# LS1_audio.net
KiCad netlist of a schematic drawn in Altium Designer
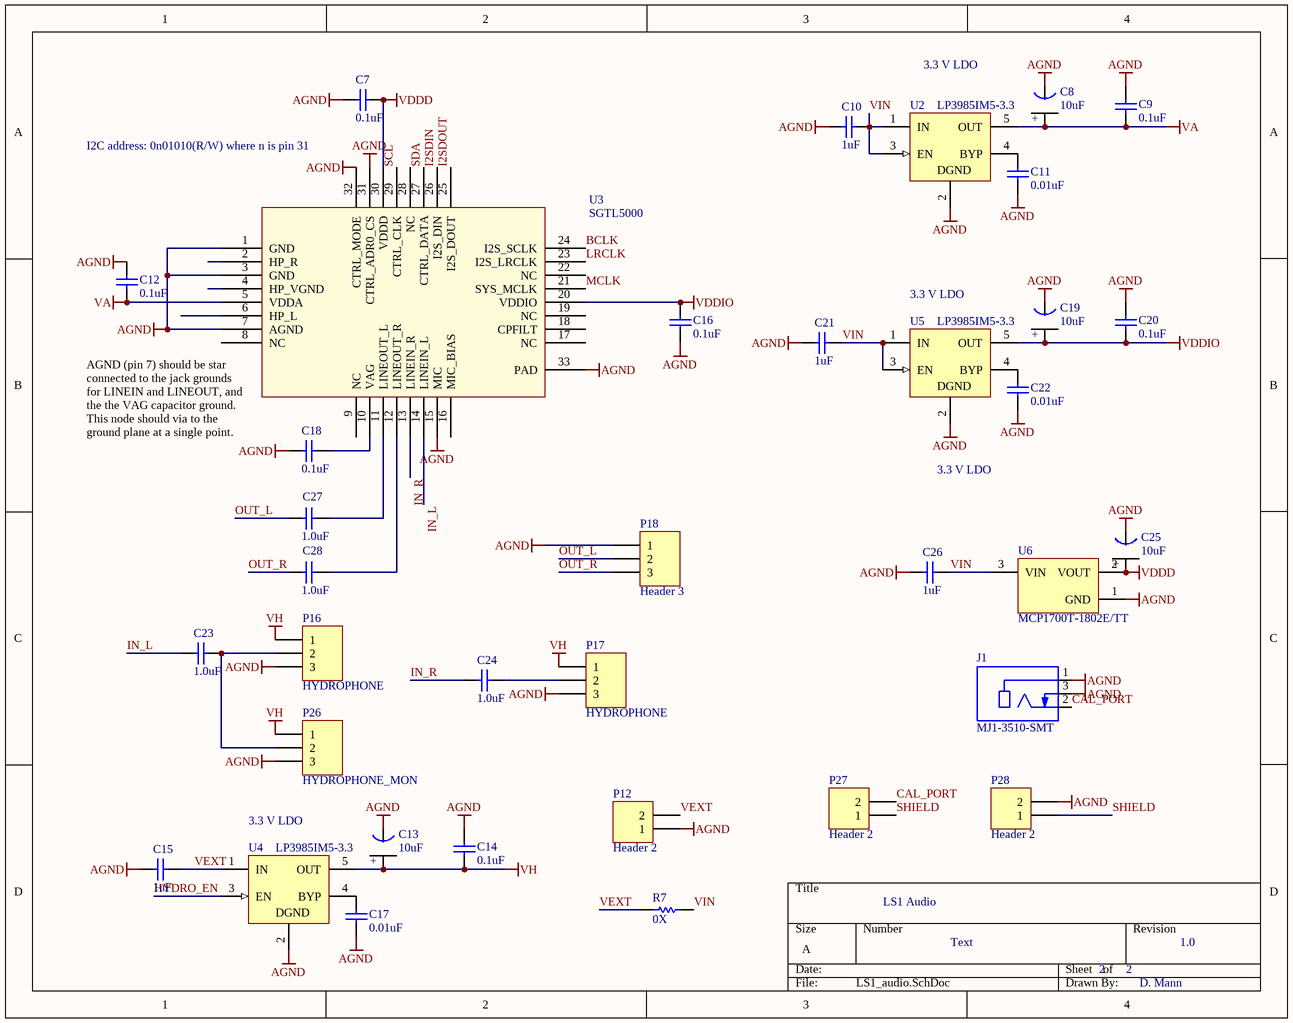
[diagram p0: LS1_audio.SchDoc]

(export (version "E")
  (design (tool "Eeschema 10.0.6"))
  (components
    (comp (ref "C7")
      (value "0.1uF")
      (footprint "0402")
      (description "Ceramic Chip Capacitor - Standard")
      (fields (field (name "PUBLISHER") "Altium Limited"))
      (libsource (lib "KEMET Chip Capacitor") (part "C0402"))
    )
    (comp (ref "C8") (value "10uF") (footprint "Tant0805") (libsource (lib "Loggerhead") (part "Tant0805")))
    (comp (ref "C9")
      (value "0.1uF")
      (footprint "0402")
      (description "Ceramic Chip Capacitor - Standard")
      (fields (field (name "PUBLISHER") "Altium Limited"))
      (libsource (lib "KEMET Chip Capacitor") (part "C0402"))
    )
    (comp (ref "C10")
      (value "1uF")
      (footprint "0402")
      (description "Ceramic Chip Capacitor - Standard")
      (fields (field (name "PUBLISHER") "Altium Limited"))
      (libsource (lib "KEMET Chip Capacitor") (part "C0402"))
    )
    (comp (ref "C11")
      (value "0.01uF")
      (footprint "0402")
      (description "Ceramic Chip Capacitor - Standard")
      (fields (field (name "PUBLISHER") "Altium Limited"))
      (libsource (lib "KEMET Chip Capacitor") (part "C0402"))
    )
    (comp (ref "C12")
      (value "0.1uF")
      (footprint "0402")
      (description "Ceramic Chip Capacitor - Standard")
      (fields (field (name "PUBLISHER") "Altium Limited"))
      (libsource (lib "KEMET Chip Capacitor") (part "C0402"))
    )
    (comp (ref "C13") (value "10uF") (footprint "Tant0805") (libsource (lib "Loggerhead") (part "Tant0805")))
    (comp (ref "C14")
      (value "0.1uF")
      (footprint "0402")
      (description "Ceramic Chip Capacitor - Standard")
      (fields (field (name "PUBLISHER") "Altium Limited"))
      (libsource (lib "KEMET Chip Capacitor") (part "C0402"))
    )
    (comp (ref "C15")
      (value "1uF")
      (footprint "0402")
      (description "Ceramic Chip Capacitor - Standard")
      (fields (field (name "PUBLISHER") "Altium Limited"))
      (libsource (lib "KEMET Chip Capacitor") (part "C0402"))
    )
    (comp (ref "C16")
      (value "0.1uF")
      (footprint "0402")
      (description "Ceramic Chip Capacitor - Standard")
      (fields (field (name "PUBLISHER") "Altium Limited"))
      (libsource (lib "KEMET Chip Capacitor") (part "C0402"))
    )
    (comp (ref "C17")
      (value "0.01uF")
      (footprint "0402")
      (description "Ceramic Chip Capacitor - Standard")
      (fields (field (name "PUBLISHER") "Altium Limited"))
      (libsource (lib "KEMET Chip Capacitor") (part "C0402"))
    )
    (comp (ref "C18")
      (value "0.1uF")
      (footprint "0402")
      (description "Ceramic Chip Capacitor - Standard")
      (fields (field (name "PUBLISHER") "Altium Limited"))
      (libsource (lib "KEMET Chip Capacitor") (part "C0402"))
    )
    (comp (ref "C19") (value "10uF") (footprint "Tant0805") (libsource (lib "Loggerhead") (part "Tant0805")))
    (comp (ref "C20")
      (value "0.1uF")
      (footprint "0402")
      (description "Ceramic Chip Capacitor - Standard")
      (fields (field (name "PUBLISHER") "Altium Limited"))
      (libsource (lib "KEMET Chip Capacitor") (part "C0402"))
    )
    (comp (ref "C21")
      (value "1uF")
      (footprint "0402")
      (description "Ceramic Chip Capacitor - Standard")
      (fields (field (name "PUBLISHER") "Altium Limited"))
      (libsource (lib "KEMET Chip Capacitor") (part "C0402"))
    )
    (comp (ref "C22")
      (value "0.01uF")
      (footprint "0402")
      (description "Ceramic Chip Capacitor - Standard")
      (fields (field (name "PUBLISHER") "Altium Limited"))
      (libsource (lib "KEMET Chip Capacitor") (part "C0402"))
    )
    (comp (ref "C23")
      (value "1.0uF")
      (footprint "0402")
      (description "Ceramic Chip Capacitor - Standard")
      (fields (field (name "PUBLISHER") "Altium Limited"))
      (libsource (lib "KEMET Chip Capacitor") (part "C0402"))
    )
    (comp (ref "C24")
      (value "1.0uF")
      (footprint "0402")
      (description "Ceramic Chip Capacitor - Standard")
      (fields (field (name "PUBLISHER") "Altium Limited"))
      (libsource (lib "KEMET Chip Capacitor") (part "C0402"))
    )
    (comp (ref "C25") (value "10uF") (footprint "Tant0805") (libsource (lib "Loggerhead") (part "Tant0805")))
    (comp (ref "C26")
      (value "1uF")
      (footprint "0402")
      (description "Ceramic Chip Capacitor - Standard")
      (fields (field (name "PUBLISHER") "Altium Limited"))
      (libsource (lib "KEMET Chip Capacitor") (part "C0402"))
    )
    (comp (ref "C27")
      (value "1.0uF")
      (footprint "0402")
      (description "Ceramic Chip Capacitor - Standard")
      (fields (field (name "PUBLISHER") "Altium Limited"))
      (libsource (lib "KEMET Chip Capacitor") (part "C0402"))
    )
    (comp (ref "C28")
      (value "1.0uF")
      (footprint "0402")
      (description "Ceramic Chip Capacitor - Standard")
      (fields (field (name "PUBLISHER") "Altium Limited"))
      (libsource (lib "KEMET Chip Capacitor") (part "C0402"))
    )
    (comp (ref "J1")
      (value "MJ1-3510-SMT")
      (footprint "CUI_MJ1-3510-SMT")
      (description "3.5 mm, Mono, Right Angle, Surface Mount (SMT), Audio Jack Connector")
      (fields (field (name "MF") "{'manufacturer': u'CUI'}"))
      (libsource (lib "MJ1-3510-SMT") (part "MJ1-3510-SMT"))
    )
    (comp (ref "P12")
      (value "Header 2")
      (footprint "HDR1X2")
      (description "Header, 2-Pin")
      (fields (field (name "PUBLISHER") "Altium Limited"))
      (libsource (lib "Miscellaneous Connectors") (part "Header 2"))
    )
    (comp (ref "P16")
      (value "HYDROPHONE")
      (footprint "HDR1X3")
      (description "Header, 3-Pin")
      (fields (field (name "PUBLISHER") "Altium Limited"))
      (libsource (lib "Miscellaneous Connectors") (part "Header 3"))
    )
    (comp (ref "P17")
      (value "HYDROPHONE")
      (footprint "HDR1X3")
      (description "Header, 3-Pin")
      (fields (field (name "PUBLISHER") "Altium Limited"))
      (libsource (lib "Miscellaneous Connectors") (part "Header 3"))
    )
    (comp (ref "P18")
      (value "Header 3")
      (footprint "HDR1X3")
      (description "Header, 3-Pin")
      (fields (field (name "PUBLISHER") "Altium Limited"))
      (libsource (lib "Miscellaneous Connectors") (part "Header 3"))
    )
    (comp (ref "P26")
      (value "HYDROPHONE_MON")
      (footprint "HDR1X3")
      (description "Header, 3-Pin")
      (fields (field (name "PUBLISHER") "Altium Limited"))
      (libsource (lib "Miscellaneous Connectors") (part "Header 3"))
    )
    (comp (ref "P27")
      (value "Header 2")
      (footprint "HDR1X2")
      (description "Header, 2-Pin")
      (fields (field (name "PUBLISHER") "Altium Limited"))
      (libsource (lib "Miscellaneous Connectors") (part "Header 2"))
    )
    (comp (ref "P28")
      (value "Header 2")
      (footprint "HDR1X2")
      (description "Header, 2-Pin")
      (fields (field (name "PUBLISHER") "Altium Limited"))
      (libsource (lib "Miscellaneous Connectors") (part "Header 2"))
    )
    (comp (ref "R7")
      (value "0X")
      (footprint "3-0603")
      (fields (field (name "PUBLISHER") "Altium Limited"))
      (libsource (lib "Panasonic Resistor") (part "ERJ3RK"))
    )
    (comp (ref "U2")
      (value "LP3985IM5-3.3")
      (footprint "MF05A_N")
      (description "Micropower, 150mA Low-Noise Ultra Low-Dropout CMOS Voltage Regulator")
      (fields
        (field (name "MANUFACTURER") "National Semiconductor")
        (field (name "DIGIKEYPARTNUMBER") "LP3985IM5-3.3CT-ND")
        (field (name "PUBLISHER") "Altium Limited")
      )
      (libsource (lib "NSC LDO") (part "LP3985IM5-3.3"))
    )
    (comp (ref "U3") (value "SGTL5000") (footprint "QFN32") (libsource (lib "Loggerhead") (part "SGTL5000")))
    (comp (ref "U4")
      (value "LP3985IM5-3.3")
      (footprint "MF05A_N")
      (description "Micropower, 150mA Low-Noise Ultra Low-Dropout CMOS Voltage Regulator")
      (fields
        (field (name "MANUFACTURER") "National Semiconductor")
        (field (name "DIGIKEYPARTNUMBER") "LP3985IM5-3.3CT-ND")
        (field (name "PUBLISHER") "Altium Limited")
      )
      (libsource (lib "NSC LDO") (part "LP3985IM5-3.3"))
    )
    (comp (ref "U5")
      (value "LP3985IM5-3.3")
      (footprint "MF05A_N")
      (description "Micropower, 150mA Low-Noise Ultra Low-Dropout CMOS Voltage Regulator")
      (fields
        (field (name "MANUFACTURER") "National Semiconductor")
        (field (name "DIGIKEYPARTNUMBER") "LP3985IM5-3.3CT-ND")
        (field (name "PUBLISHER") "Altium Limited")
      )
      (libsource (lib "NSC LDO") (part "LP3985IM5-3.3"))
    )
    (comp (ref "U6")
      (value "MCP1700T-1802E/TT")
      (footprint "SOT-23-TT3_N")
      (description "Low Quiescent Current LDO, 3-Pin SOT-23, Extended Temperature, Tape and Reel")
      (fields (field (name "MANUFACTURER") "Microchip"))
      (libsource (lib "Microchip Power Management Line Regulator") (part "MCP1700T-1802E/TT"))
    )
  )
  (nets
    (net (code "1") (name "/BCLK") (class "Default")
      (node (ref "U3") (pin "24") (pinfunction "I2S_SCLK_24") (pintype "passive"))
    )
    (net (code "2") (name "/CAL_PORT") (class "Default")
      (node (ref "J1") (pin "2") (pinfunction "2_2") (pintype "passive"))
      (node (ref "P27") (pin "2") (pinfunction "2_2") (pintype "passive"))
    )
    (net (code "3") (name "/HYDRO_EN") (class "Default")
      (node (ref "U4") (pin "3") (pinfunction "EN_3") (pintype "input"))
    )
    (net (code "4") (name "/I2SDIN") (class "Default")
      (node (ref "U3") (pin "26") (pinfunction "I2S_DIN_26") (pintype "passive"))
    )
    (net (code "5") (name "/I2SDOUT") (class "Default")
      (node (ref "U3") (pin "25") (pinfunction "I2S_DOUT_25") (pintype "passive"))
    )
    (net (code "6") (name "/IN_L") (class "Default")
      (node (ref "C23") (pin "2") (pinfunction "2_2") (pintype "passive"))
      (node (ref "U3") (pin "14") (pinfunction "LINEIN_L_14") (pintype "passive"))
    )
    (net (code "7") (name "/IN_R") (class "Default")
      (node (ref "C24") (pin "2") (pinfunction "2_2") (pintype "passive"))
      (node (ref "U3") (pin "13") (pinfunction "LINEIN_R_13") (pintype "passive"))
    )
    (net (code "8") (name "/LRCLK") (class "Default")
      (node (ref "U3") (pin "23") (pinfunction "I2S_LRCLK_23") (pintype "passive"))
    )
    (net (code "9") (name "/MCLK") (class "Default")
      (node (ref "U3") (pin "21") (pinfunction "SYS_MCLK_21") (pintype "passive"))
    )
    (net (code "10") (name "/OUT_L") (class "Default")
      (node (ref "C27") (pin "1") (pinfunction "1_1") (pintype "passive"))
      (node (ref "P18") (pin "2") (pinfunction "2_2") (pintype "passive"))
    )
    (net (code "11") (name "/OUT_R") (class "Default")
      (node (ref "C28") (pin "1") (pinfunction "1_1") (pintype "passive"))
      (node (ref "P18") (pin "3") (pinfunction "3_3") (pintype "passive"))
    )
    (net (code "12") (name "/SCL") (class "Default")
      (node (ref "U3") (pin "29") (pinfunction "CTRL_CLK_29") (pintype "passive"))
    )
    (net (code "13") (name "/SDA") (class "Default")
      (node (ref "U3") (pin "27") (pinfunction "CTRL_DATA_27") (pintype "passive"))
    )
    (net (code "14") (name "/SHIELD") (class "Default")
      (node (ref "P27") (pin "1") (pinfunction "1_1") (pintype "passive"))
      (node (ref "P28") (pin "1") (pinfunction "1_1") (pintype "passive"))
    )
    (net (code "15") (name "/VEXT") (class "Default")
      (node (ref "C15") (pin "1") (pinfunction "1_1") (pintype "passive"))
      (node (ref "P12") (pin "2") (pinfunction "2_2") (pintype "passive"))
      (node (ref "R7") (pin "2") (pinfunction "2_2") (pintype "passive"))
      (node (ref "U4") (pin "1") (pinfunction "IN_1") (pintype "power_in"))
    )
    (net (code "16") (name "/VIN") (class "Default")
      (node (ref "C10") (pin "1") (pinfunction "1_1") (pintype "passive"))
      (node (ref "C21") (pin "1") (pinfunction "1_1") (pintype "passive"))
      (node (ref "C26") (pin "1") (pinfunction "1_1") (pintype "passive"))
      (node (ref "R7") (pin "1") (pinfunction "1_1") (pintype "passive"))
      (node (ref "U2") (pin "1") (pinfunction "IN_1") (pintype "power_in"))
      (node (ref "U2") (pin "3") (pinfunction "EN_3") (pintype "input"))
      (node (ref "U5") (pin "1") (pinfunction "IN_1") (pintype "power_in"))
      (node (ref "U5") (pin "3") (pinfunction "EN_3") (pintype "input"))
      (node (ref "U6") (pin "3") (pinfunction "VIN_3") (pintype "power_in"))
    )
    (net (code "17") (name "AGND") (class "Default")
      (node (ref "C10") (pin "2") (pinfunction "2_2") (pintype "passive"))
      (node (ref "C11") (pin "2") (pinfunction "2_2") (pintype "passive"))
      (node (ref "C12") (pin "2") (pinfunction "2_2") (pintype "passive"))
      (node (ref "C13") (pin "1") (pinfunction "GND_1") (pintype "passive"))
      (node (ref "C14") (pin "2") (pinfunction "2_2") (pintype "passive"))
      (node (ref "C15") (pin "2") (pinfunction "2_2") (pintype "passive"))
      (node (ref "C16") (pin "2") (pinfunction "2_2") (pintype "passive"))
      (node (ref "C17") (pin "2") (pinfunction "2_2") (pintype "passive"))
      (node (ref "C18") (pin "2") (pinfunction "2_2") (pintype "passive"))
      (node (ref "C19") (pin "1") (pinfunction "GND_1") (pintype "passive"))
      (node (ref "C20") (pin "2") (pinfunction "2_2") (pintype "passive"))
      (node (ref "C21") (pin "2") (pinfunction "2_2") (pintype "passive"))
      (node (ref "C22") (pin "2") (pinfunction "2_2") (pintype "passive"))
      (node (ref "C25") (pin "1") (pinfunction "GND_1") (pintype "passive"))
      (node (ref "C26") (pin "2") (pinfunction "2_2") (pintype "passive"))
      (node (ref "C7") (pin "2") (pinfunction "2_2") (pintype "passive"))
      (node (ref "C8") (pin "1") (pinfunction "GND_1") (pintype "passive"))
      (node (ref "C9") (pin "2") (pinfunction "2_2") (pintype "passive"))
      (node (ref "J1") (pin "1") (pinfunction "1_1") (pintype "passive"))
      (node (ref "J1") (pin "3") (pinfunction "3_3") (pintype "passive"))
      (node (ref "P12") (pin "1") (pinfunction "1_1") (pintype "passive"))
      (node (ref "P16") (pin "3") (pinfunction "3_3") (pintype "passive"))
      (node (ref "P17") (pin "3") (pinfunction "3_3") (pintype "passive"))
      (node (ref "P18") (pin "1") (pinfunction "1_1") (pintype "passive"))
      (node (ref "P26") (pin "3") (pinfunction "3_3") (pintype "passive"))
      (node (ref "P28") (pin "2") (pinfunction "2_2") (pintype "passive"))
      (node (ref "U2") (pin "2") (pinfunction "GND_2") (pintype "power_in"))
      (node (ref "U3") (pin "1") (pinfunction "GND_1") (pintype "passive"))
      (node (ref "U3") (pin "15") (pinfunction "MIC_15") (pintype "passive"))
      (node (ref "U3") (pin "3") (pinfunction "GND_3") (pintype "passive"))
      (node (ref "U3") (pin "31") (pinfunction "CTRL_ADR0_CS_31") (pintype "passive"))
      (node (ref "U3") (pin "32") (pinfunction "CTRL_MODE_32") (pintype "passive"))
      (node (ref "U3") (pin "33") (pinfunction "PAD_33") (pintype "passive"))
      (node (ref "U3") (pin "7") (pinfunction "AGND_7") (pintype "passive"))
      (node (ref "U4") (pin "2") (pinfunction "GND_2") (pintype "power_in"))
      (node (ref "U5") (pin "2") (pinfunction "GND_2") (pintype "power_in"))
      (node (ref "U6") (pin "1") (pinfunction "GND_1") (pintype "power_in"))
    )
    (net (code "18") (name "Net-(C23-Pad1)") (class "Default")
      (node (ref "C23") (pin "1") (pinfunction "1_1") (pintype "passive"))
      (node (ref "P16") (pin "2") (pinfunction "2_2") (pintype "passive"))
      (node (ref "P26") (pin "2") (pinfunction "2_2") (pintype "passive"))
    )
    (net (code "19") (name "Net-(C24-Pad1)") (class "Default")
      (node (ref "C24") (pin "1") (pinfunction "1_1") (pintype "passive"))
      (node (ref "P17") (pin "2") (pinfunction "2_2") (pintype "passive"))
    )
    (net (code "20") (name "Net-(U2-BYP)") (class "Default")
      (node (ref "C11") (pin "1") (pinfunction "1_1") (pintype "passive"))
      (node (ref "U2") (pin "4") (pinfunction "BYP_4") (pintype "passive"))
    )
    (net (code "21") (name "Net-(U3-LINEOUT_L)") (class "Default")
      (node (ref "C27") (pin "2") (pinfunction "2_2") (pintype "passive"))
      (node (ref "U3") (pin "11") (pinfunction "LINEOUT_L_11") (pintype "passive"))
    )
    (net (code "22") (name "Net-(U3-LINEOUT_R)") (class "Default")
      (node (ref "C28") (pin "2") (pinfunction "2_2") (pintype "passive"))
      (node (ref "U3") (pin "12") (pinfunction "LINEOUT_R_12") (pintype "passive"))
    )
    (net (code "23") (name "Net-(U3-VAG)") (class "Default")
      (node (ref "C18") (pin "1") (pinfunction "1_1") (pintype "passive"))
      (node (ref "U3") (pin "10") (pinfunction "VAG_10") (pintype "passive"))
    )
    (net (code "24") (name "Net-(U4-BYP)") (class "Default")
      (node (ref "C17") (pin "1") (pinfunction "1_1") (pintype "passive"))
      (node (ref "U4") (pin "4") (pinfunction "BYP_4") (pintype "passive"))
    )
    (net (code "25") (name "Net-(U5-BYP)") (class "Default")
      (node (ref "C22") (pin "1") (pinfunction "1_1") (pintype "passive"))
      (node (ref "U5") (pin "4") (pinfunction "BYP_4") (pintype "passive"))
    )
    (net (code "26") (name "VA") (class "Default")
      (node (ref "C12") (pin "1") (pinfunction "1_1") (pintype "passive"))
      (node (ref "C8") (pin "2") (pinfunction "+_2") (pintype "passive"))
      (node (ref "C9") (pin "1") (pinfunction "1_1") (pintype "passive"))
      (node (ref "U2") (pin "5") (pinfunction "OUT_5") (pintype "power_in"))
      (node (ref "U3") (pin "5") (pinfunction "VDDA_5") (pintype "passive"))
    )
    (net (code "27") (name "VDDD") (class "Default")
      (node (ref "C25") (pin "2") (pinfunction "+_2") (pintype "passive"))
      (node (ref "C7") (pin "1") (pinfunction "1_1") (pintype "passive"))
      (node (ref "U3") (pin "30") (pinfunction "VDDD_30") (pintype "passive"))
      (node (ref "U6") (pin "2") (pinfunction "VOUT_2") (pintype "power_in"))
    )
    (net (code "28") (name "VDDIO") (class "Default")
      (node (ref "C16") (pin "1") (pinfunction "1_1") (pintype "passive"))
      (node (ref "C19") (pin "2") (pinfunction "+_2") (pintype "passive"))
      (node (ref "C20") (pin "1") (pinfunction "1_1") (pintype "passive"))
      (node (ref "U3") (pin "20") (pinfunction "VDDIO_20") (pintype "passive"))
      (node (ref "U5") (pin "5") (pinfunction "OUT_5") (pintype "power_in"))
    )
    (net (code "29") (name "VH") (class "Default")
      (node (ref "C13") (pin "2") (pinfunction "+_2") (pintype "passive"))
      (node (ref "C14") (pin "1") (pinfunction "1_1") (pintype "passive"))
      (node (ref "P16") (pin "1") (pinfunction "1_1") (pintype "passive"))
      (node (ref "P17") (pin "1") (pinfunction "1_1") (pintype "passive"))
      (node (ref "P26") (pin "1") (pinfunction "1_1") (pintype "passive"))
      (node (ref "U4") (pin "5") (pinfunction "OUT_5") (pintype "power_in"))
    )
    (net (code "30") (name "unconnected-(U3-CPFILT-Pad18)") (class "Default")
      (node (ref "U3") (pin "18") (pinfunction "CPFILT_18") (pintype "passive"))
    )
    (net (code "31") (name "unconnected-(U3-HP_L-Pad6)") (class "Default")
      (node (ref "U3") (pin "6") (pinfunction "HP_L_6") (pintype "passive"))
    )
    (net (code "32") (name "unconnected-(U3-HP_R-Pad2)") (class "Default")
      (node (ref "U3") (pin "2") (pinfunction "HP_R_2") (pintype "passive"))
    )
    (net (code "33") (name "unconnected-(U3-HP_VGND-Pad4)") (class "Default")
      (node (ref "U3") (pin "4") (pinfunction "HP_VGND_4") (pintype "passive"))
    )
    (net (code "34") (name "unconnected-(U3-MIC_BIAS-Pad16)") (class "Default")
      (node (ref "U3") (pin "16") (pinfunction "MIC_BIAS_16") (pintype "passive"))
    )
    (net (code "35") (name "unconnected-(U3-NC-Pad8)") (class "Default")
      (node (ref "U3") (pin "8") (pinfunction "NC_8") (pintype "passive"))
    )
    (net (code "36") (name "unconnected-(U3-NC-Pad9)") (class "Default")
      (node (ref "U3") (pin "9") (pinfunction "NC_9") (pintype "passive"))
    )
    (net (code "37") (name "unconnected-(U3-NC-Pad17)") (class "Default")
      (node (ref "U3") (pin "17") (pinfunction "NC_17") (pintype "passive"))
    )
    (net (code "38") (name "unconnected-(U3-NC-Pad19)") (class "Default")
      (node (ref "U3") (pin "19") (pinfunction "NC_19") (pintype "passive"))
    )
    (net (code "39") (name "unconnected-(U3-NC-Pad22)") (class "Default")
      (node (ref "U3") (pin "22") (pinfunction "NC_22") (pintype "passive"))
    )
    (net (code "40") (name "unconnected-(U3-NC-Pad28)") (class "Default")
      (node (ref "U3") (pin "28") (pinfunction "NC_28") (pintype "passive"))
    )
  )
)
